# GMSL_SERIALIZER.net
KiCad netlist of a schematic drawn in Altium Designer
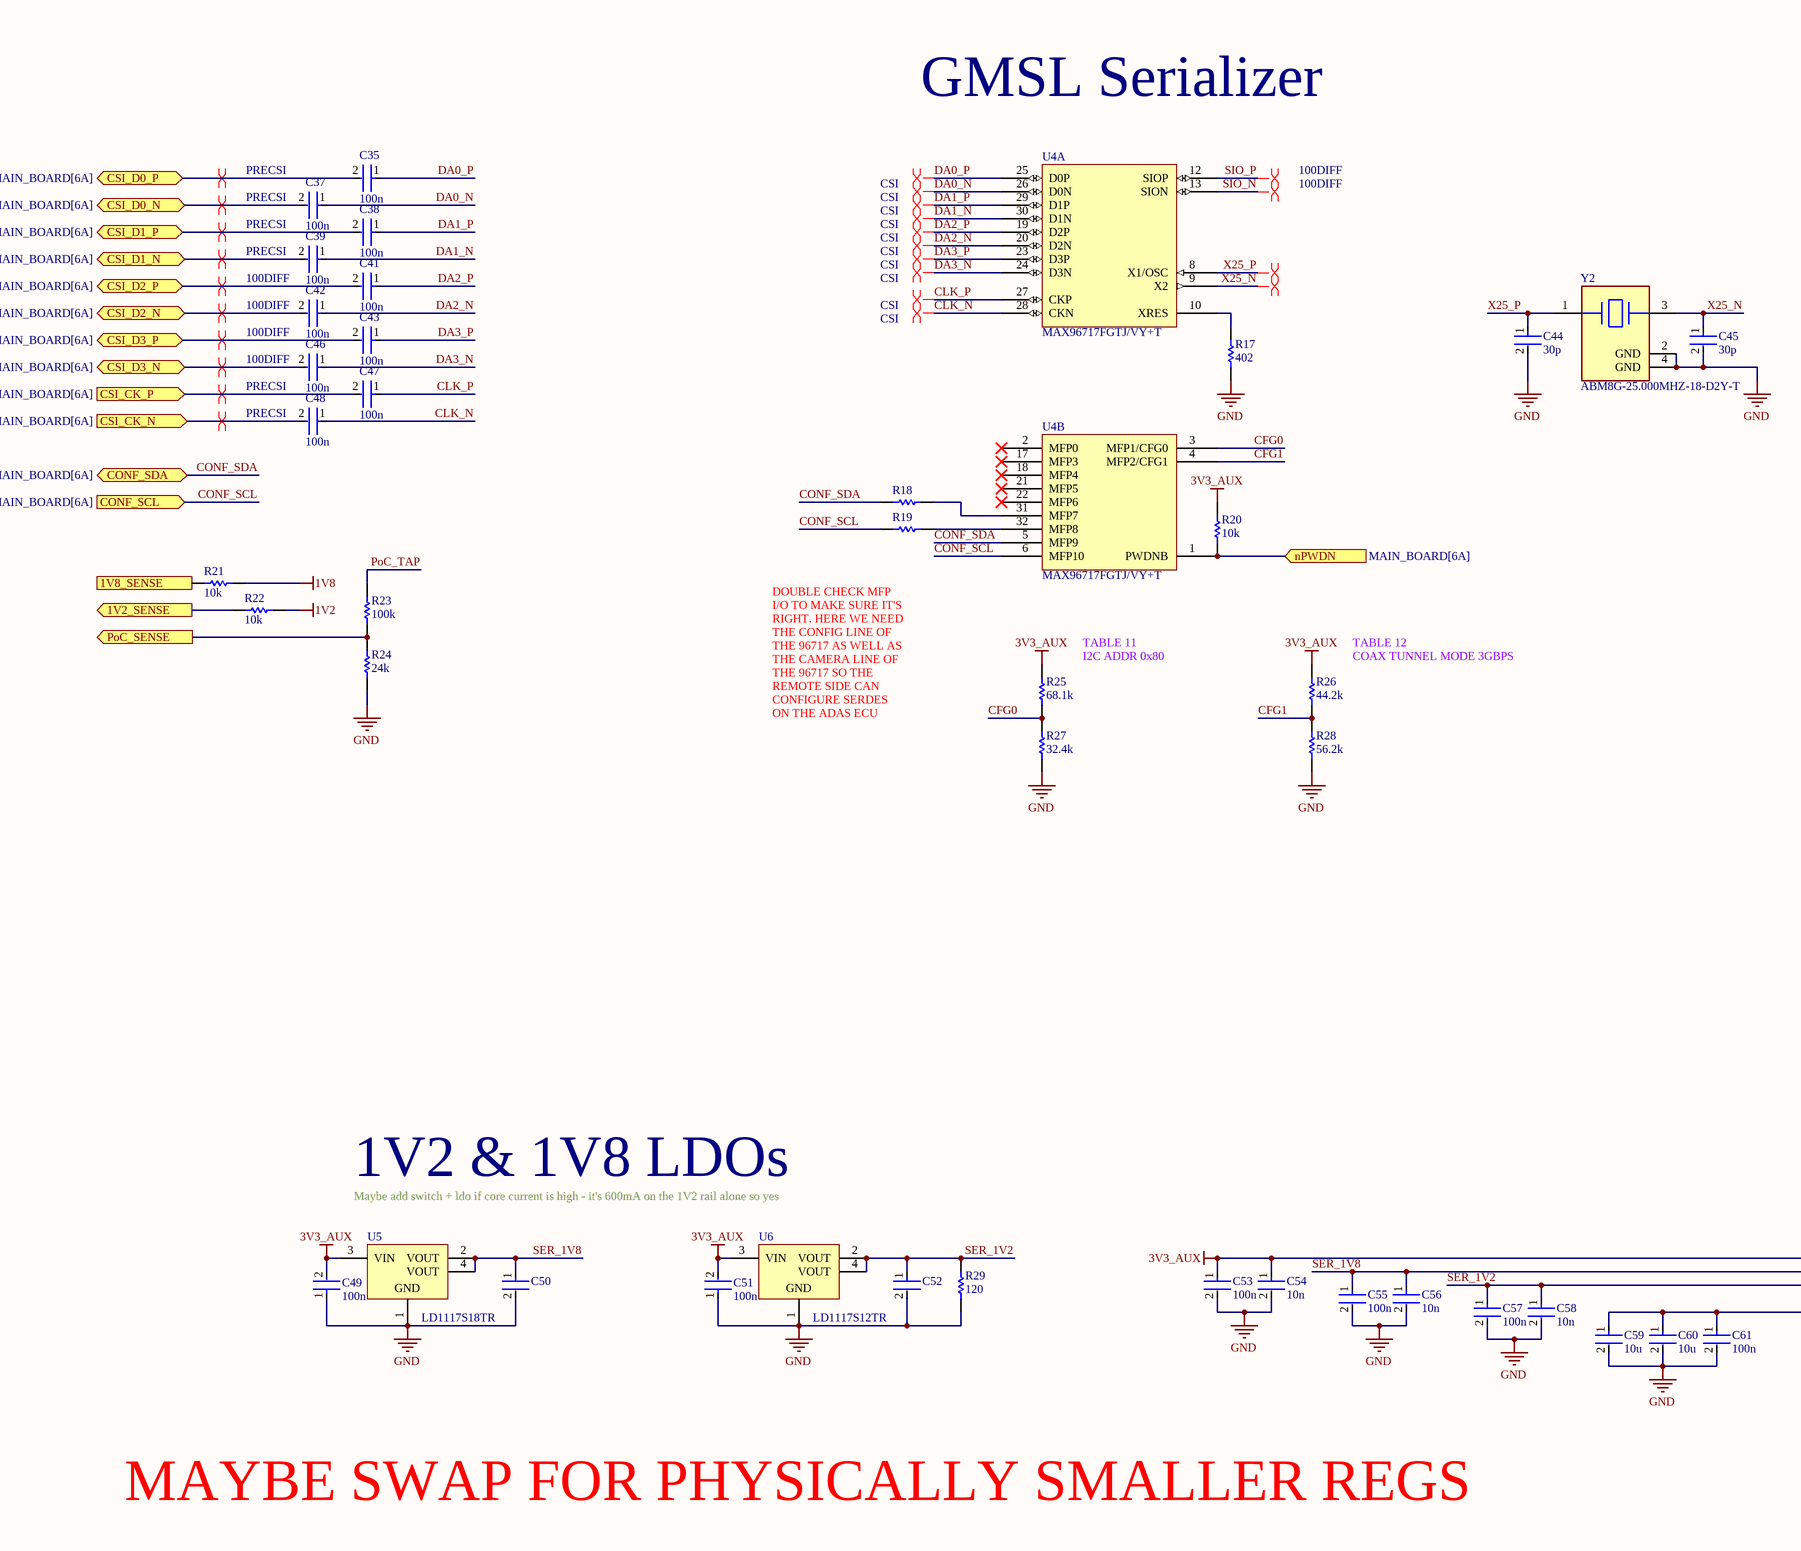
[diagram p0: GMSL_SERIALIZER.SchDoc, left]
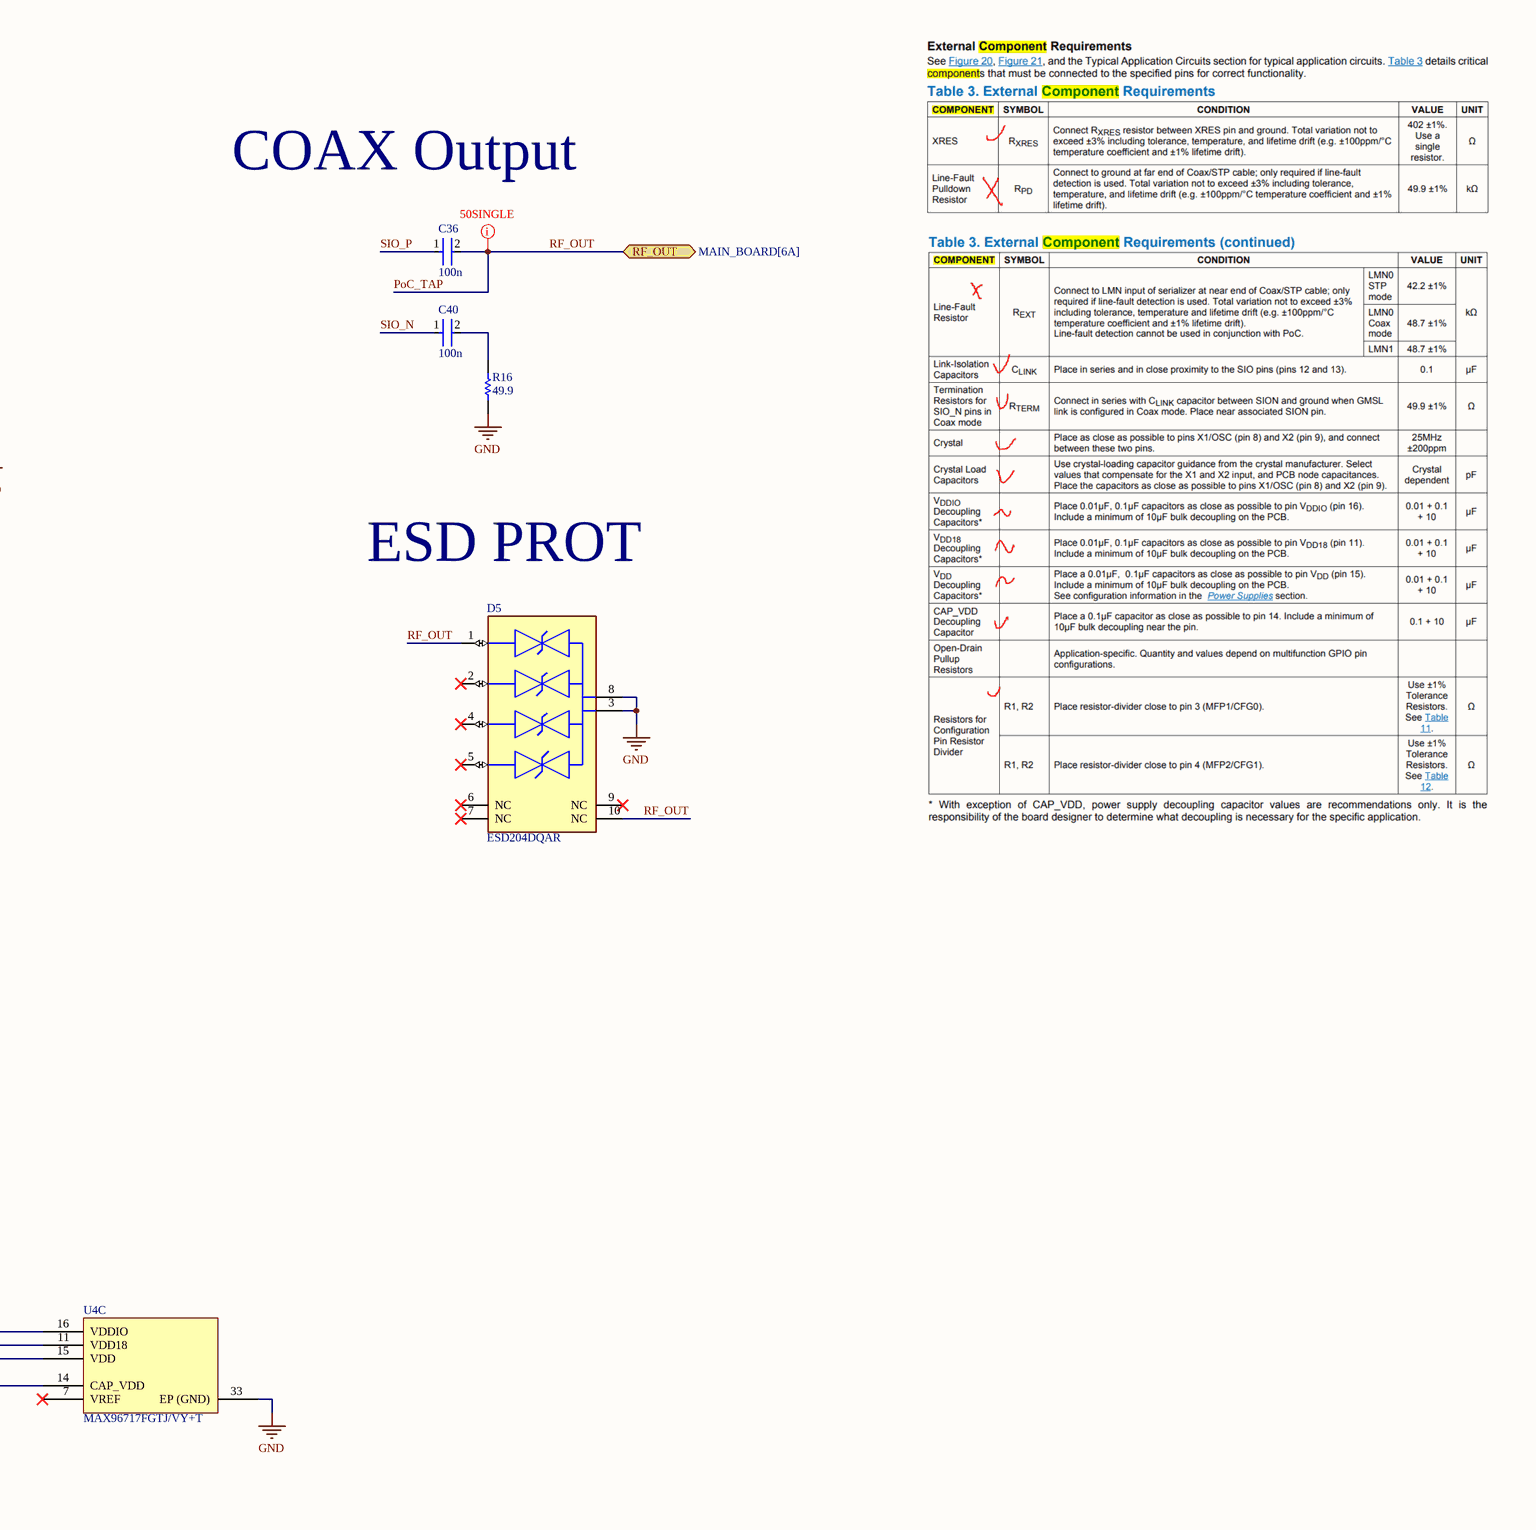
[diagram p1: GMSL_SERIALIZER.SchDoc, right]

(export (version "E")
  (design (tool "Eeschema 10.0.6"))
  (components
    (comp (ref "C35")
      (value "100n")
      (footprint "FP-0402-L_1_0_0_05-W_0_5-IPC_A")
      (description "LARGE PADS, 0402 CAP, CHANGE COMMENT TO MATCH REAL P/N")
      (libsource (lib "Space Concordia") (part "b4654b650e69147ec39a6b967a45e02"))
    )
    (comp (ref "C36")
      (value "100n")
      (footprint "FP-0402-L_1_0_0_05-W_0_5-IPC_A")
      (description "LARGE PADS, 0402 CAP, CHANGE COMMENT TO MATCH REAL P/N")
      (libsource (lib "Space Concordia") (part "b4654b650e69147ec39a6b967a45e02"))
    )
    (comp (ref "C37")
      (value "100n")
      (footprint "FP-0402-L_1_0_0_05-W_0_5-IPC_A")
      (description "LARGE PADS, 0402 CAP, CHANGE COMMENT TO MATCH REAL P/N")
      (libsource (lib "Space Concordia") (part "b4654b650e69147ec39a6b967a45e02"))
    )
    (comp (ref "C38")
      (value "100n")
      (footprint "FP-0402-L_1_0_0_05-W_0_5-IPC_A")
      (description "LARGE PADS, 0402 CAP, CHANGE COMMENT TO MATCH REAL P/N")
      (libsource (lib "Space Concordia") (part "b4654b650e69147ec39a6b967a45e02"))
    )
    (comp (ref "C39")
      (value "100n")
      (footprint "FP-0402-L_1_0_0_05-W_0_5-IPC_A")
      (description "LARGE PADS, 0402 CAP, CHANGE COMMENT TO MATCH REAL P/N")
      (libsource (lib "Space Concordia") (part "b4654b650e69147ec39a6b967a45e02"))
    )
    (comp (ref "C40")
      (value "100n")
      (footprint "FP-0402-L_1_0_0_05-W_0_5-IPC_A")
      (description "LARGE PADS, 0402 CAP, CHANGE COMMENT TO MATCH REAL P/N")
      (libsource (lib "Space Concordia") (part "b4654b650e69147ec39a6b967a45e02"))
    )
    (comp (ref "C41")
      (value "100n")
      (footprint "FP-0402-L_1_0_0_05-W_0_5-IPC_A")
      (description "LARGE PADS, 0402 CAP, CHANGE COMMENT TO MATCH REAL P/N")
      (libsource (lib "Space Concordia") (part "b4654b650e69147ec39a6b967a45e02"))
    )
    (comp (ref "C42")
      (value "100n")
      (footprint "FP-0402-L_1_0_0_05-W_0_5-IPC_A")
      (description "LARGE PADS, 0402 CAP, CHANGE COMMENT TO MATCH REAL P/N")
      (libsource (lib "Space Concordia") (part "b4654b650e69147ec39a6b967a45e02"))
    )
    (comp (ref "C43")
      (value "100n")
      (footprint "FP-0402-L_1_0_0_05-W_0_5-IPC_A")
      (description "LARGE PADS, 0402 CAP, CHANGE COMMENT TO MATCH REAL P/N")
      (libsource (lib "Space Concordia") (part "b4654b650e69147ec39a6b967a45e02"))
    )
    (comp (ref "C44")
      (value "30p")
      (footprint "FP-0402-L_1_0_0_05-W_0_5-IPC_A")
      (description "LARGE PADS, 0402 CAP, CHANGE COMMENT TO MATCH REAL P/N")
      (libsource (lib "Space Concordia") (part "b4654b650e69147ec39a6b967a45e02"))
    )
    (comp (ref "C45")
      (value "30p")
      (footprint "FP-0402-L_1_0_0_05-W_0_5-IPC_A")
      (description "LARGE PADS, 0402 CAP, CHANGE COMMENT TO MATCH REAL P/N")
      (libsource (lib "Space Concordia") (part "b4654b650e69147ec39a6b967a45e02"))
    )
    (comp (ref "C46")
      (value "100n")
      (footprint "FP-0402-L_1_0_0_05-W_0_5-IPC_A")
      (description "LARGE PADS, 0402 CAP, CHANGE COMMENT TO MATCH REAL P/N")
      (libsource (lib "Space Concordia") (part "b4654b650e69147ec39a6b967a45e02"))
    )
    (comp (ref "C47")
      (value "100n")
      (footprint "FP-0402-L_1_0_0_05-W_0_5-IPC_A")
      (description "LARGE PADS, 0402 CAP, CHANGE COMMENT TO MATCH REAL P/N")
      (libsource (lib "Space Concordia") (part "b4654b650e69147ec39a6b967a45e02"))
    )
    (comp (ref "C48")
      (value "100n")
      (footprint "FP-0402-L_1_0_0_05-W_0_5-IPC_A")
      (description "LARGE PADS, 0402 CAP, CHANGE COMMENT TO MATCH REAL P/N")
      (libsource (lib "Space Concordia") (part "b4654b650e69147ec39a6b967a45e02"))
    )
    (comp (ref "C49")
      (value "100n")
      (footprint "FP-0402-L_1_0_0_05-W_0_5-IPC_A")
      (description "LARGE PADS, 0402 CAP, CHANGE COMMENT TO MATCH REAL P/N")
      (libsource (lib "Space Concordia") (part "b4654b650e69147ec39a6b967a45e02"))
    )
    (comp (ref "C50")
      (value "GRM188R60J106ME47D")
      (footprint "FP-GRM188-0_1-e0_2_0_55-IPC_A")
      (description "Chip Multilayer Ceramic Capacitors for General Purpose, 0603, 10uF, X5R, 15%, 20%, 6.3V")
      (fields (field (name "VOLTAGE") "6.3V") (field (name "TOLERANCE") "20%"))
      (libsource (lib "Altium Content Vault") (part "02cd4be3c70576c341d710602a673aa"))
    )
    (comp (ref "C51")
      (value "100n")
      (footprint "FP-0402-L_1_0_0_05-W_0_5-IPC_A")
      (description "LARGE PADS, 0402 CAP, CHANGE COMMENT TO MATCH REAL P/N")
      (libsource (lib "Space Concordia") (part "b4654b650e69147ec39a6b967a45e02"))
    )
    (comp (ref "C52")
      (value "GRM188R60J106ME47D")
      (footprint "FP-GRM188-0_1-e0_2_0_55-IPC_A")
      (description "Chip Multilayer Ceramic Capacitors for General Purpose, 0603, 10uF, X5R, 15%, 20%, 6.3V")
      (fields (field (name "VOLTAGE") "6.3V") (field (name "TOLERANCE") "20%"))
      (libsource (lib "Altium Content Vault") (part "02cd4be3c70576c341d710602a673aa"))
    )
    (comp (ref "C53")
      (value "100n")
      (footprint "FP-0402-L_1_0_0_05-W_0_5-IPC_A")
      (description "LARGE PADS, 0402 CAP, CHANGE COMMENT TO MATCH REAL P/N")
      (libsource (lib "Space Concordia") (part "b4654b650e69147ec39a6b967a45e02"))
    )
    (comp (ref "C54")
      (value "10n")
      (footprint "FP-0402-L_1_0_0_05-W_0_5-IPC_A")
      (description "LARGE PADS, 0402 CAP, CHANGE COMMENT TO MATCH REAL P/N")
      (libsource (lib "Space Concordia") (part "b4654b650e69147ec39a6b967a45e02"))
    )
    (comp (ref "C55")
      (value "100n")
      (footprint "FP-0402-L_1_0_0_05-W_0_5-IPC_A")
      (description "LARGE PADS, 0402 CAP, CHANGE COMMENT TO MATCH REAL P/N")
      (libsource (lib "Space Concordia") (part "b4654b650e69147ec39a6b967a45e02"))
    )
    (comp (ref "C56")
      (value "10n")
      (footprint "FP-0402-L_1_0_0_05-W_0_5-IPC_A")
      (description "LARGE PADS, 0402 CAP, CHANGE COMMENT TO MATCH REAL P/N")
      (libsource (lib "Space Concordia") (part "b4654b650e69147ec39a6b967a45e02"))
    )
    (comp (ref "C57")
      (value "100n")
      (footprint "FP-0402-L_1_0_0_05-W_0_5-IPC_A")
      (description "LARGE PADS, 0402 CAP, CHANGE COMMENT TO MATCH REAL P/N")
      (libsource (lib "Space Concordia") (part "b4654b650e69147ec39a6b967a45e02"))
    )
    (comp (ref "C58")
      (value "10n")
      (footprint "FP-0402-L_1_0_0_05-W_0_5-IPC_A")
      (description "LARGE PADS, 0402 CAP, CHANGE COMMENT TO MATCH REAL P/N")
      (libsource (lib "Space Concordia") (part "b4654b650e69147ec39a6b967a45e02"))
    )
    (comp (ref "C59")
      (value "10u")
      (footprint "FP-0402-L_1_0_0_05-W_0_5-IPC_A")
      (description "LARGE PADS, 0402 CAP, CHANGE COMMENT TO MATCH REAL P/N")
      (libsource (lib "Space Concordia") (part "b4654b650e69147ec39a6b967a45e02"))
    )
    (comp (ref "C60")
      (value "10u")
      (footprint "FP-0402-L_1_0_0_05-W_0_5-IPC_A")
      (description "LARGE PADS, 0402 CAP, CHANGE COMMENT TO MATCH REAL P/N")
      (libsource (lib "Space Concordia") (part "b4654b650e69147ec39a6b967a45e02"))
    )
    (comp (ref "C61")
      (value "100n")
      (footprint "FP-0402-L_1_0_0_05-W_0_5-IPC_A")
      (description "LARGE PADS, 0402 CAP, CHANGE COMMENT TO MATCH REAL P/N")
      (libsource (lib "Space Concordia") (part "b4654b650e69147ec39a6b967a45e02"))
    )
    (comp (ref "D5")
      (value "ESD204DQAR")
      (footprint "FP-DQA0010A-MFG")
      (description "4-CHANNEL LOW-CAPACITANCE SURGE")
      (fields
        (field (name "MANUFACTURER") "Texas Instruments")
        (field (name "OCTOPART") "https://octopart.com/esd204dqar-texas+instruments-89917476")
      )
      (libsource (lib "Altium Content Vault") (part "1465e58c1818c7767b55926832f0bf5"))
    )
    (comp (ref "R16")
      (value "49.9")
      (footprint "R0603B")
      (description "Resistor")
      (libsource (lib "Space Concordia") (part "Resistor"))
    )
    (comp (ref "R17")
      (value "402")
      (footprint "R0603B")
      (description "Resistor")
      (libsource (lib "Space Concordia") (part "Resistor"))
    )
    (comp (ref "R18")
      (value "0402 JUMPER")
      (footprint "RESC1005X40X25ML05T05")
      (description "READ THE NAME")
      (libsource (lib "Space Concordia") (part "CMP-009-00206-2"))
    )
    (comp (ref "R19")
      (value "0402 JUMPER")
      (footprint "RESC1005X40X25ML05T05")
      (description "READ THE NAME")
      (libsource (lib "Space Concordia") (part "CMP-009-00206-2"))
    )
    (comp (ref "R20")
      (value "10k")
      (footprint "R0603B")
      (description "Resistor")
      (libsource (lib "Space Concordia") (part "Resistor"))
    )
    (comp (ref "R21")
      (value "10k")
      (footprint "R0603B")
      (description "Resistor")
      (libsource (lib "Space Concordia") (part "Resistor"))
    )
    (comp (ref "R22")
      (value "10k")
      (footprint "R0603B")
      (description "Resistor")
      (libsource (lib "Space Concordia") (part "Resistor"))
    )
    (comp (ref "R23")
      (value "100k")
      (footprint "R0603B")
      (description "Resistor")
      (libsource (lib "Space Concordia") (part "Resistor"))
    )
    (comp (ref "R24")
      (value "24k")
      (footprint "R0603B")
      (description "Resistor")
      (libsource (lib "Space Concordia") (part "Resistor"))
    )
    (comp (ref "R25")
      (value "68.1k")
      (footprint "R0603B")
      (description "Resistor")
      (libsource (lib "Space Concordia") (part "Resistor"))
    )
    (comp (ref "R26")
      (value "44.2k")
      (footprint "R0603B")
      (description "Resistor")
      (libsource (lib "Space Concordia") (part "Resistor"))
    )
    (comp (ref "R27")
      (value "32.4k")
      (footprint "R0603B")
      (description "Resistor")
      (libsource (lib "Space Concordia") (part "Resistor"))
    )
    (comp (ref "R28")
      (value "56.2k")
      (footprint "R0603B")
      (description "Resistor")
      (libsource (lib "Space Concordia") (part "Resistor"))
    )
    (comp (ref "R29")
      (value "120")
      (footprint "R0603B")
      (description "Resistor")
      (libsource (lib "Space Concordia") (part "Resistor"))
    )
    (comp (ref "U4")
      (value "MAX96717FGTJ/VY+T")
      (footprint "QFN50P500X500X80_HS-33N")
      (description "3Gbps Serializer TQFN-32 Serializers / Deserializers ROHS")
      (libsource (lib "Space Concordia") (part "MAX96717FGTJ_VY+T"))
    )
    (comp (ref "U5")
      (value "LD1117S18TR")
      (footprint "SOT-223_M")
      (description "Fixed Low Drop Positive Voltage Regulator, 1.8V, 4-Pin SOT-223, Tape and Reel")
      (libsource (lib "Altium Content Vault") (part "PM-REG-LD1117-SOT4"))
    )
    (comp (ref "U6")
      (value "LD1117S12TR")
      (footprint "SOT-223_M")
      (description "Fixed Low Drop Positive Voltage Regulator, 1.2V, 4-Pin SOT-223, Tape and Reel")
      (libsource (lib "Altium Content Vault") (part "PM-REG-LD1117-SOT4"))
    )
    (comp (ref "Y2")
      (value "ABM8G-25.000MHZ-18-D2Y-T")
      (footprint "FP-ABM8G-MFG")
      (description "Crystal 25MHz ±20ppm (Tol) ±30ppm (Stability) 18pF FUND 60Ω 4-Pin SMD T/R")
      (fields (field (name "TOLERANCE") "20ppm"))
      (libsource (lib "Altium Content Vault") (part "48e526d86b7f2615d98721063c72f49"))
    )
  )
  (nets
    (net (code "1") (name "/1V2_SENSE") (class "Default")
      (node (ref "R22") (pin "2") (pinfunction "2_2") (pintype "passive"))
    )
    (net (code "2") (name "/1V8_SENSE") (class "Default")
      (node (ref "R21") (pin "2") (pinfunction "2_2") (pintype "passive"))
    )
    (net (code "3") (name "/CFG0") (class "Default")
      (node (ref "R25") (pin "1") (pinfunction "1_1") (pintype "passive"))
      (node (ref "R27") (pin "2") (pinfunction "2_2") (pintype "passive"))
      (node (ref "U4") (pin "3") (pinfunction "MFP1/CFG0_3") (pintype "passive"))
    )
    (net (code "4") (name "/CFG1") (class "Default")
      (node (ref "R26") (pin "1") (pinfunction "1_1") (pintype "passive"))
      (node (ref "R28") (pin "2") (pinfunction "2_2") (pintype "passive"))
      (node (ref "U4") (pin "4") (pinfunction "MFP2/CFG1_4") (pintype "passive"))
    )
    (net (code "5") (name "/CLK_N") (class "Default")
      (node (ref "C48") (pin "1") (pinfunction "1_1") (pintype "passive"))
      (node (ref "U4") (pin "28") (pinfunction "CKN_28") (pintype "bidirectional"))
    )
    (net (code "6") (name "/CLK_P") (class "Default")
      (node (ref "C47") (pin "1") (pinfunction "1_1") (pintype "passive"))
      (node (ref "U4") (pin "27") (pinfunction "CKP_27") (pintype "bidirectional"))
    )
    (net (code "7") (name "/CONF_SCL") (class "Default")
      (node (ref "R19") (pin "1") (pinfunction "1_1") (pintype "passive"))
      (node (ref "U4") (pin "6") (pinfunction "MFP10_6") (pintype "passive"))
    )
    (net (code "8") (name "/CONF_SDA") (class "Default")
      (node (ref "R18") (pin "1") (pinfunction "1_1") (pintype "passive"))
      (node (ref "U4") (pin "5") (pinfunction "MFP9_5") (pintype "passive"))
    )
    (net (code "9") (name "/CSI_CK_N") (class "Default")
      (node (ref "C48") (pin "2") (pinfunction "2_2") (pintype "passive"))
    )
    (net (code "10") (name "/CSI_CK_P") (class "Default")
      (node (ref "C47") (pin "2") (pinfunction "2_2") (pintype "passive"))
    )
    (net (code "11") (name "/CSI_D0_N") (class "Default")
      (node (ref "C37") (pin "2") (pinfunction "2_2") (pintype "passive"))
    )
    (net (code "12") (name "/CSI_D0_P") (class "Default")
      (node (ref "C35") (pin "2") (pinfunction "2_2") (pintype "passive"))
    )
    (net (code "13") (name "/CSI_D1_N") (class "Default")
      (node (ref "C39") (pin "2") (pinfunction "2_2") (pintype "passive"))
    )
    (net (code "14") (name "/CSI_D1_P") (class "Default")
      (node (ref "C38") (pin "2") (pinfunction "2_2") (pintype "passive"))
    )
    (net (code "15") (name "/CSI_D2_N") (class "Default")
      (node (ref "C42") (pin "2") (pinfunction "2_2") (pintype "passive"))
    )
    (net (code "16") (name "/CSI_D2_P") (class "Default")
      (node (ref "C41") (pin "2") (pinfunction "2_2") (pintype "passive"))
    )
    (net (code "17") (name "/CSI_D3_N") (class "Default")
      (node (ref "C46") (pin "2") (pinfunction "2_2") (pintype "passive"))
    )
    (net (code "18") (name "/CSI_D3_P") (class "Default")
      (node (ref "C43") (pin "2") (pinfunction "2_2") (pintype "passive"))
    )
    (net (code "19") (name "/DA0_N") (class "Default")
      (node (ref "C37") (pin "1") (pinfunction "1_1") (pintype "passive"))
      (node (ref "U4") (pin "26") (pinfunction "D0N_26") (pintype "bidirectional"))
    )
    (net (code "20") (name "/DA0_P") (class "Default")
      (node (ref "C35") (pin "1") (pinfunction "1_1") (pintype "passive"))
      (node (ref "U4") (pin "25") (pinfunction "D0P_25") (pintype "bidirectional"))
    )
    (net (code "21") (name "/DA1_N") (class "Default")
      (node (ref "C39") (pin "1") (pinfunction "1_1") (pintype "passive"))
      (node (ref "U4") (pin "30") (pinfunction "D1N_30") (pintype "bidirectional"))
    )
    (net (code "22") (name "/DA1_P") (class "Default")
      (node (ref "C38") (pin "1") (pinfunction "1_1") (pintype "passive"))
      (node (ref "U4") (pin "29") (pinfunction "D1P_29") (pintype "bidirectional"))
    )
    (net (code "23") (name "/DA2_N") (class "Default")
      (node (ref "C42") (pin "1") (pinfunction "1_1") (pintype "passive"))
      (node (ref "U4") (pin "20") (pinfunction "D2N_20") (pintype "bidirectional"))
    )
    (net (code "24") (name "/DA2_P") (class "Default")
      (node (ref "C41") (pin "1") (pinfunction "1_1") (pintype "passive"))
      (node (ref "U4") (pin "19") (pinfunction "D2P_19") (pintype "bidirectional"))
    )
    (net (code "25") (name "/DA3_N") (class "Default")
      (node (ref "C46") (pin "1") (pinfunction "1_1") (pintype "passive"))
      (node (ref "U4") (pin "24") (pinfunction "D3N_24") (pintype "bidirectional"))
    )
    (net (code "26") (name "/DA3_P") (class "Default")
      (node (ref "C43") (pin "1") (pinfunction "1_1") (pintype "passive"))
      (node (ref "U4") (pin "23") (pinfunction "D3P_23") (pintype "bidirectional"))
    )
    (net (code "27") (name "/PoC_SENSE") (class "Default")
      (node (ref "R23") (pin "1") (pinfunction "1_1") (pintype "passive"))
      (node (ref "R24") (pin "2") (pinfunction "2_2") (pintype "passive"))
    )
    (net (code "28") (name "/PoC_TAP") (class "Default")
      (node (ref "C36") (pin "2") (pinfunction "2_2") (pintype "passive"))
      (node (ref "D5") (pin "1") (pinfunction "IO1_1") (pintype "bidirectional"))
      (node (ref "D5") (pin "10") (pinfunction "NC_10") (pintype "passive"))
      (node (ref "R23") (pin "2") (pinfunction "2_2") (pintype "passive"))
    )
    (net (code "29") (name "/SER_1V2") (class "Default")
      (node (ref "C52") (pin "1") (pinfunction "1_1") (pintype "passive"))
      (node (ref "C57") (pin "1") (pinfunction "1_1") (pintype "passive"))
      (node (ref "C58") (pin "1") (pinfunction "1_1") (pintype "passive"))
      (node (ref "R29") (pin "2") (pinfunction "2_2") (pintype "passive"))
      (node (ref "U4") (pin "15") (pinfunction "VDD_15") (pintype "power_in"))
      (node (ref "U6") (pin "2") (pinfunction "VOUT_2") (pintype "power_in"))
      (node (ref "U6") (pin "4") (pinfunction "VOUT_4") (pintype "power_in"))
    )
    (net (code "30") (name "/SER_1V8") (class "Default")
      (node (ref "C50") (pin "1") (pinfunction "1_1") (pintype "passive"))
      (node (ref "C55") (pin "1") (pinfunction "1_1") (pintype "passive"))
      (node (ref "C56") (pin "1") (pinfunction "1_1") (pintype "passive"))
      (node (ref "U4") (pin "11") (pinfunction "VDD18_11") (pintype "power_in"))
      (node (ref "U5") (pin "2") (pinfunction "VOUT_2") (pintype "power_in"))
      (node (ref "U5") (pin "4") (pinfunction "VOUT_4") (pintype "power_in"))
    )
    (net (code "31") (name "/SIO_N") (class "Default")
      (node (ref "C40") (pin "1") (pinfunction "1_1") (pintype "passive"))
      (node (ref "U4") (pin "13") (pinfunction "SION_13") (pintype "bidirectional"))
    )
    (net (code "32") (name "/SIO_P") (class "Default")
      (node (ref "C36") (pin "1") (pinfunction "1_1") (pintype "passive"))
      (node (ref "U4") (pin "12") (pinfunction "SIOP_12") (pintype "bidirectional"))
    )
    (net (code "33") (name "/X25_N") (class "Default")
      (node (ref "C45") (pin "1") (pinfunction "1_1") (pintype "passive"))
      (node (ref "U4") (pin "9") (pinfunction "X2_9") (pintype "output"))
      (node (ref "Y2") (pin "3") (pinfunction "3_3") (pintype "passive"))
    )
    (net (code "34") (name "/X25_P") (class "Default")
      (node (ref "C44") (pin "1") (pinfunction "1_1") (pintype "passive"))
      (node (ref "U4") (pin "8") (pinfunction "X1/OSC_8") (pintype "input"))
      (node (ref "Y2") (pin "1") (pinfunction "1_1") (pintype "passive"))
    )
    (net (code "35") (name "/nPWDN") (class "Default")
      (node (ref "R20") (pin "1") (pinfunction "1_1") (pintype "passive"))
      (node (ref "U4") (pin "1") (pinfunction "PWDNB_1") (pintype "passive"))
    )
    (net (code "36") (name "1V2") (class "Default")
      (node (ref "R22") (pin "1") (pinfunction "1_1") (pintype "passive"))
    )
    (net (code "37") (name "1V8") (class "Default")
      (node (ref "R21") (pin "1") (pinfunction "1_1") (pintype "passive"))
    )
    (net (code "38") (name "3V3_AUX") (class "Default")
      (node (ref "C49") (pin "2") (pinfunction "2_2") (pintype "passive"))
      (node (ref "C51") (pin "2") (pinfunction "2_2") (pintype "passive"))
      (node (ref "C53") (pin "1") (pinfunction "1_1") (pintype "passive"))
      (node (ref "C54") (pin "1") (pinfunction "1_1") (pintype "passive"))
      (node (ref "R20") (pin "2") (pinfunction "2_2") (pintype "passive"))
      (node (ref "R25") (pin "2") (pinfunction "2_2") (pintype "passive"))
      (node (ref "R26") (pin "2") (pinfunction "2_2") (pintype "passive"))
      (node (ref "U4") (pin "16") (pinfunction "VDDIO_16") (pintype "power_in"))
      (node (ref "U5") (pin "3") (pinfunction "VIN_3") (pintype "power_in"))
      (node (ref "U6") (pin "3") (pinfunction "VIN_3") (pintype "power_in"))
    )
    (net (code "39") (name "GND") (class "Default")
      (node (ref "C44") (pin "2") (pinfunction "2_2") (pintype "passive"))
      (node (ref "C45") (pin "2") (pinfunction "2_2") (pintype "passive"))
      (node (ref "C49") (pin "1") (pinfunction "1_1") (pintype "passive"))
      (node (ref "C50") (pin "2") (pinfunction "2_2") (pintype "passive"))
      (node (ref "C51") (pin "1") (pinfunction "1_1") (pintype "passive"))
      (node (ref "C52") (pin "2") (pinfunction "2_2") (pintype "passive"))
      (node (ref "C53") (pin "2") (pinfunction "2_2") (pintype "passive"))
      (node (ref "C54") (pin "2") (pinfunction "2_2") (pintype "passive"))
      (node (ref "C55") (pin "2") (pinfunction "2_2") (pintype "passive"))
      (node (ref "C56") (pin "2") (pinfunction "2_2") (pintype "passive"))
      (node (ref "C57") (pin "2") (pinfunction "2_2") (pintype "passive"))
      (node (ref "C58") (pin "2") (pinfunction "2_2") (pintype "passive"))
      (node (ref "C59") (pin "2") (pinfunction "2_2") (pintype "passive"))
      (node (ref "C60") (pin "2") (pinfunction "2_2") (pintype "passive"))
      (node (ref "C61") (pin "2") (pinfunction "2_2") (pintype "passive"))
      (node (ref "D5") (pin "3") (pinfunction "GND_3") (pintype "power_in"))
      (node (ref "D5") (pin "8") (pinfunction "GND_8") (pintype "power_in"))
      (node (ref "R16") (pin "1") (pinfunction "1_1") (pintype "passive"))
      (node (ref "R17") (pin "1") (pinfunction "1_1") (pintype "passive"))
      (node (ref "R24") (pin "1") (pinfunction "1_1") (pintype "passive"))
      (node (ref "R27") (pin "1") (pinfunction "1_1") (pintype "passive"))
      (node (ref "R28") (pin "1") (pinfunction "1_1") (pintype "passive"))
      (node (ref "R29") (pin "1") (pinfunction "1_1") (pintype "passive"))
      (node (ref "U4") (pin "33") (pinfunction "EP_(GND)_33") (pintype "power_in"))
      (node (ref "U5") (pin "1") (pinfunction "GND_1") (pintype "power_in"))
      (node (ref "U6") (pin "1") (pinfunction "GND_1") (pintype "power_in"))
      (node (ref "Y2") (pin "2") (pinfunction "GND_2") (pintype "power_in"))
      (node (ref "Y2") (pin "4") (pinfunction "GND_4") (pintype "power_in"))
    )
    (net (code "40") (name "Net-(C40-Pad2)") (class "Default")
      (node (ref "C40") (pin "2") (pinfunction "2_2") (pintype "passive"))
      (node (ref "R16") (pin "2") (pinfunction "2_2") (pintype "passive"))
    )
    (net (code "41") (name "Net-(U4A-XRES)") (class "Default")
      (node (ref "R17") (pin "2") (pinfunction "2_2") (pintype "passive"))
      (node (ref "U4") (pin "10") (pinfunction "XRES_10") (pintype "passive"))
    )
    (net (code "42") (name "Net-(U4B-MFP7)") (class "Default")
      (node (ref "R18") (pin "2") (pinfunction "2_2") (pintype "passive"))
      (node (ref "U4") (pin "31") (pinfunction "MFP7_31") (pintype "passive"))
    )
    (net (code "43") (name "Net-(U4B-MFP8)") (class "Default")
      (node (ref "R19") (pin "2") (pinfunction "2_2") (pintype "passive"))
      (node (ref "U4") (pin "32") (pinfunction "MFP8_32") (pintype "passive"))
    )
    (net (code "44") (name "Net-(U4C-CAP_VDD)") (class "Default")
      (node (ref "C59") (pin "1") (pinfunction "1_1") (pintype "passive"))
      (node (ref "C60") (pin "1") (pinfunction "1_1") (pintype "passive"))
      (node (ref "C61") (pin "1") (pinfunction "1_1") (pintype "passive"))
      (node (ref "U4") (pin "14") (pinfunction "CAP_VDD_14") (pintype "power_in"))
    )
    (net (code "45") (name "unconnected-(D5-IO2-Pad2)") (class "Default")
      (node (ref "D5") (pin "2") (pinfunction "IO2_2") (pintype "bidirectional+no_connect"))
    )
    (net (code "46") (name "unconnected-(D5-IO3-Pad4)") (class "Default")
      (node (ref "D5") (pin "4") (pinfunction "IO3_4") (pintype "bidirectional+no_connect"))
    )
    (net (code "47") (name "unconnected-(D5-IO4-Pad5)") (class "Default")
      (node (ref "D5") (pin "5") (pinfunction "IO4_5") (pintype "bidirectional+no_connect"))
    )
    (net (code "48") (name "unconnected-(D5-NC-Pad6)") (class "Default")
      (node (ref "D5") (pin "6") (pinfunction "NC_6") (pintype "passive+no_connect"))
    )
    (net (code "49") (name "unconnected-(D5-NC-Pad7)") (class "Default")
      (node (ref "D5") (pin "7") (pinfunction "NC_7") (pintype "passive+no_connect"))
    )
    (net (code "50") (name "unconnected-(D5-NC-Pad9)") (class "Default")
      (node (ref "D5") (pin "9") (pinfunction "NC_9") (pintype "passive+no_connect"))
    )
    (net (code "51") (name "unconnected-(U4B-MFP0-Pad2)") (class "Default")
      (node (ref "U4") (pin "2") (pinfunction "MFP0_2") (pintype "passive+no_connect"))
    )
    (net (code "52") (name "unconnected-(U4B-MFP3-Pad17)") (class "Default")
      (node (ref "U4") (pin "17") (pinfunction "MFP3_17") (pintype "passive+no_connect"))
    )
    (net (code "53") (name "unconnected-(U4B-MFP4-Pad18)") (class "Default")
      (node (ref "U4") (pin "18") (pinfunction "MFP4_18") (pintype "passive+no_connect"))
    )
    (net (code "54") (name "unconnected-(U4B-MFP5-Pad21)") (class "Default")
      (node (ref "U4") (pin "21") (pinfunction "MFP5_21") (pintype "passive+no_connect"))
    )
    (net (code "55") (name "unconnected-(U4B-MFP6-Pad22)") (class "Default")
      (node (ref "U4") (pin "22") (pinfunction "MFP6_22") (pintype "passive+no_connect"))
    )
    (net (code "56") (name "unconnected-(U4C-VREF-Pad7)") (class "Default")
      (node (ref "U4") (pin "7") (pinfunction "VREF_7") (pintype "power_in+no_connect"))
    )
  )
)
